# LM2596.net
KiCad netlist of a schematic drawn in EAGLE
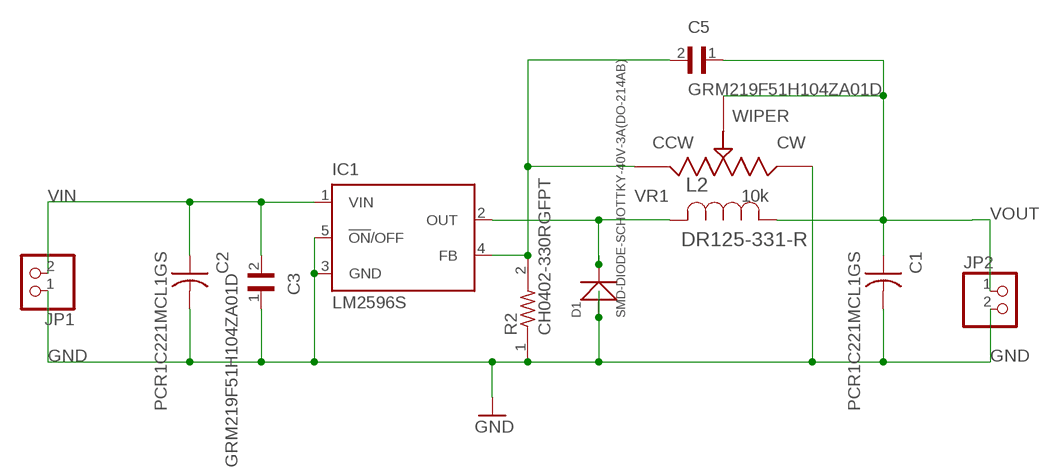
[diagram p0: schematic, sheet 1]

(export (version "E")
  (design (tool "Eeschema 10.0.6"))
  (components
    (comp (ref "C1")
      (value "PCR1C221MCL1GS")
      (footprint "eagle-import:CAPE830X690N")
      (fields (field (name "MF") "Nichicon"))
      (libsource (lib "eagle-import") (part "PCR1C221MCL1GS"))
    )
    (comp (ref "C2")
      (value "PCR1C221MCL1GS")
      (footprint "eagle-import:CAPE830X690N")
      (fields (field (name "MF") "Nichicon"))
      (libsource (lib "eagle-import") (part "PCR1C221MCL1GS"))
    )
    (comp (ref "C3")
      (value "GRM219F51H104ZA01D")
      (footprint "eagle-import:CAPC2012X135N")
      (fields (field (name "MF") "Murata Electronics"))
      (libsource (lib "eagle-import") (part "GRM219F51H104ZA01D"))
    )
    (comp (ref "C5")
      (value "GRM219F51H104ZA01D")
      (footprint "eagle-import:CAPC2012X135N")
      (fields (field (name "MF") "Murata Electronics"))
      (libsource (lib "eagle-import") (part "GRM219F51H104ZA01D"))
    )
    (comp (ref "D1")
      (value "SMD-DIODE-SCHOTTKY-40V-3A(DO-214AB)")
      (footprint "eagle-import:DO-214AB")
      (fields
        (field (name "DIGI-KEY_PART_NUMBER") "SS34-E3/57TGICT-ND")
        (field (name "MF") "Vishay")
        (field (name "MP") "SS34-E3/57T")
      )
      (libsource (lib "eagle-import") (part "SMD-DIODE-SCHOTTKY-40V-3A(DO-214AB)"))
    )
    (comp (ref "IC1")
      (value "LM2596S")
      (footprint "eagle-import:TO263-5")
      (fields (field (name "MF") "NATIONAL SEMICONDUCTOR") (field (name "MPN") "LM2596S-ADJ/NOPB"))
      (libsource (lib "eagle-import") (part "LM2596S"))
    )
    (comp (ref "JP1")
      (value "PINHD-1X2/90")
      (footprint "eagle-import:1X02_90")
      (libsource (lib "eagle-import") (part "PINHD-1X2/90"))
    )
    (comp (ref "JP2")
      (value "PINHD-1X2/90")
      (footprint "eagle-import:1X02_90")
      (libsource (lib "eagle-import") (part "PINHD-1X2/90"))
    )
    (comp (ref "L2")
      (value "DR125-331-R")
      (footprint "eagle-import:INDM125125X600N")
      (fields (field (name "MF") "Eaton"))
      (libsource (lib "eagle-import") (part "DR125-331-R"))
    )
    (comp (ref "R2")
      (value "CH0402-330RGFPT")
      (footprint "eagle-import:RESC1005X40")
      (fields (field (name "MF") "Vishay"))
      (libsource (lib "eagle-import") (part "CH0402-330RGFPT"))
    )
    (comp (ref "VR1")
      (value "10k")
      (footprint "eagle-import:W")
      (fields
        (field (name "MANUFACTURER") "Bourns Inc")
        (field (name "PART_NUMBER") "3296W-1-103LF")
        (field (name "POWER") "0.5W, 1/2W")
      )
      (libsource (lib "eagle-import") (part "3296?-W1-103LF"))
    )
  )
  (nets
    (net (code "1") (name "GND") (class "Default")
      (node (ref "C1") (pin "2") (pinfunction "-_2") (pintype "passive"))
      (node (ref "C2") (pin "2") (pinfunction "-_2") (pintype "passive"))
      (node (ref "C3") (pin "1") (pinfunction "1_1") (pintype "passive"))
      (node (ref "D1") (pin "1") (pinfunction "+_1") (pintype "passive"))
      (node (ref "IC1") (pin "3") (pinfunction "GND_3") (pintype "power_in"))
      (node (ref "IC1") (pin "5") (pinfunction "~{ON}/OFF_5") (pintype "input"))
      (node (ref "JP1") (pin "1") (pinfunction "1_1") (pintype "passive"))
      (node (ref "JP2") (pin "2") (pinfunction "2_2") (pintype "passive"))
      (node (ref "R2") (pin "1") (pinfunction "1_1") (pintype "passive"))
      (node (ref "VR1") (pin "3") (pinfunction "3_3") (pintype "passive"))
    )
    (net (code "2") (name "Net-(D1--)") (class "Default")
      (node (ref "D1") (pin "2") (pinfunction "-_2") (pintype "passive"))
      (node (ref "IC1") (pin "2") (pinfunction "OUT_2") (pintype "output"))
      (node (ref "L2") (pin "2") (pinfunction "2_2") (pintype "passive"))
    )
    (net (code "3") (name "Net-(IC1-FB)") (class "Default")
      (node (ref "C5") (pin "2") (pinfunction "2_2") (pintype "passive"))
      (node (ref "IC1") (pin "4") (pinfunction "FB_4") (pintype "input"))
      (node (ref "R2") (pin "2") (pinfunction "2_2") (pintype "passive"))
      (node (ref "VR1") (pin "1") (pinfunction "1_1") (pintype "passive"))
    )
    (net (code "4") (name "VIN") (class "Default")
      (node (ref "C2") (pin "1") (pinfunction "+_1") (pintype "passive"))
      (node (ref "C3") (pin "2") (pinfunction "2_2") (pintype "passive"))
      (node (ref "IC1") (pin "1") (pinfunction "VIN_1") (pintype "input"))
      (node (ref "JP1") (pin "2") (pinfunction "2_2") (pintype "passive"))
    )
    (net (code "5") (name "VOUT") (class "Default")
      (node (ref "C1") (pin "1") (pinfunction "+_1") (pintype "passive"))
      (node (ref "C5") (pin "1") (pinfunction "1_1") (pintype "passive"))
      (node (ref "JP2") (pin "1") (pinfunction "1_1") (pintype "passive"))
      (node (ref "L2") (pin "1") (pinfunction "1_1") (pintype "passive"))
      (node (ref "VR1") (pin "2") (pinfunction "2_2") (pintype "passive"))
    )
  )
)
